# 39-VOLTAGE_SUPERVISOR_AND_WKUP_LEDs.net
KiCad netlist of a schematic drawn in Altium Designer
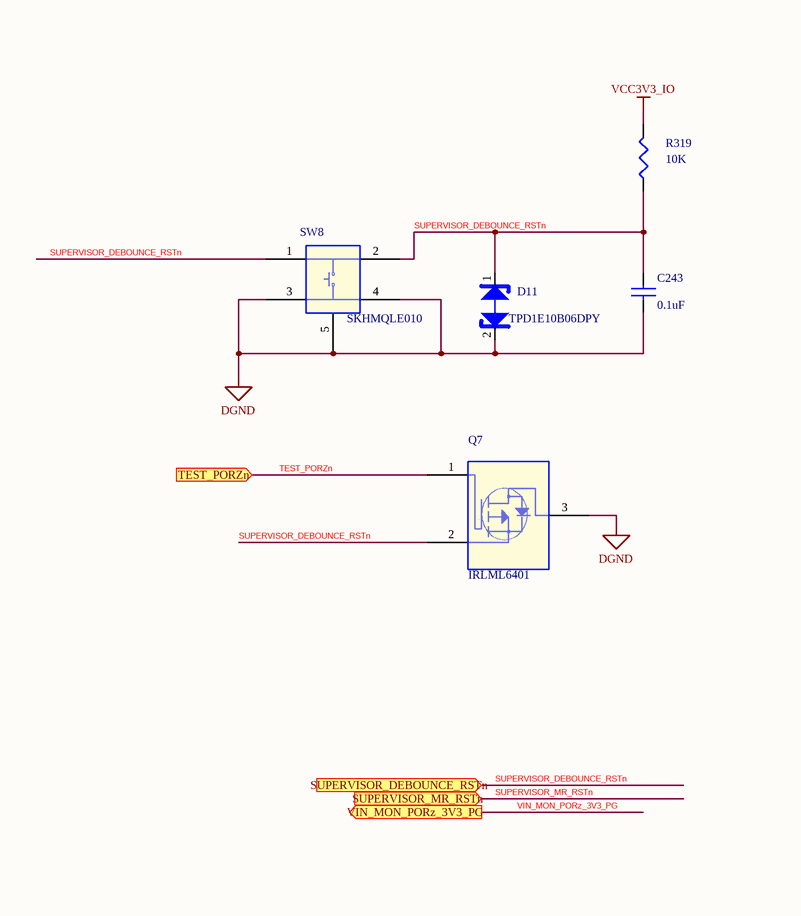
[diagram p0: 39-VOLTAGE SUPERVISOR AND WKUP LEDs.SchDoc, left]
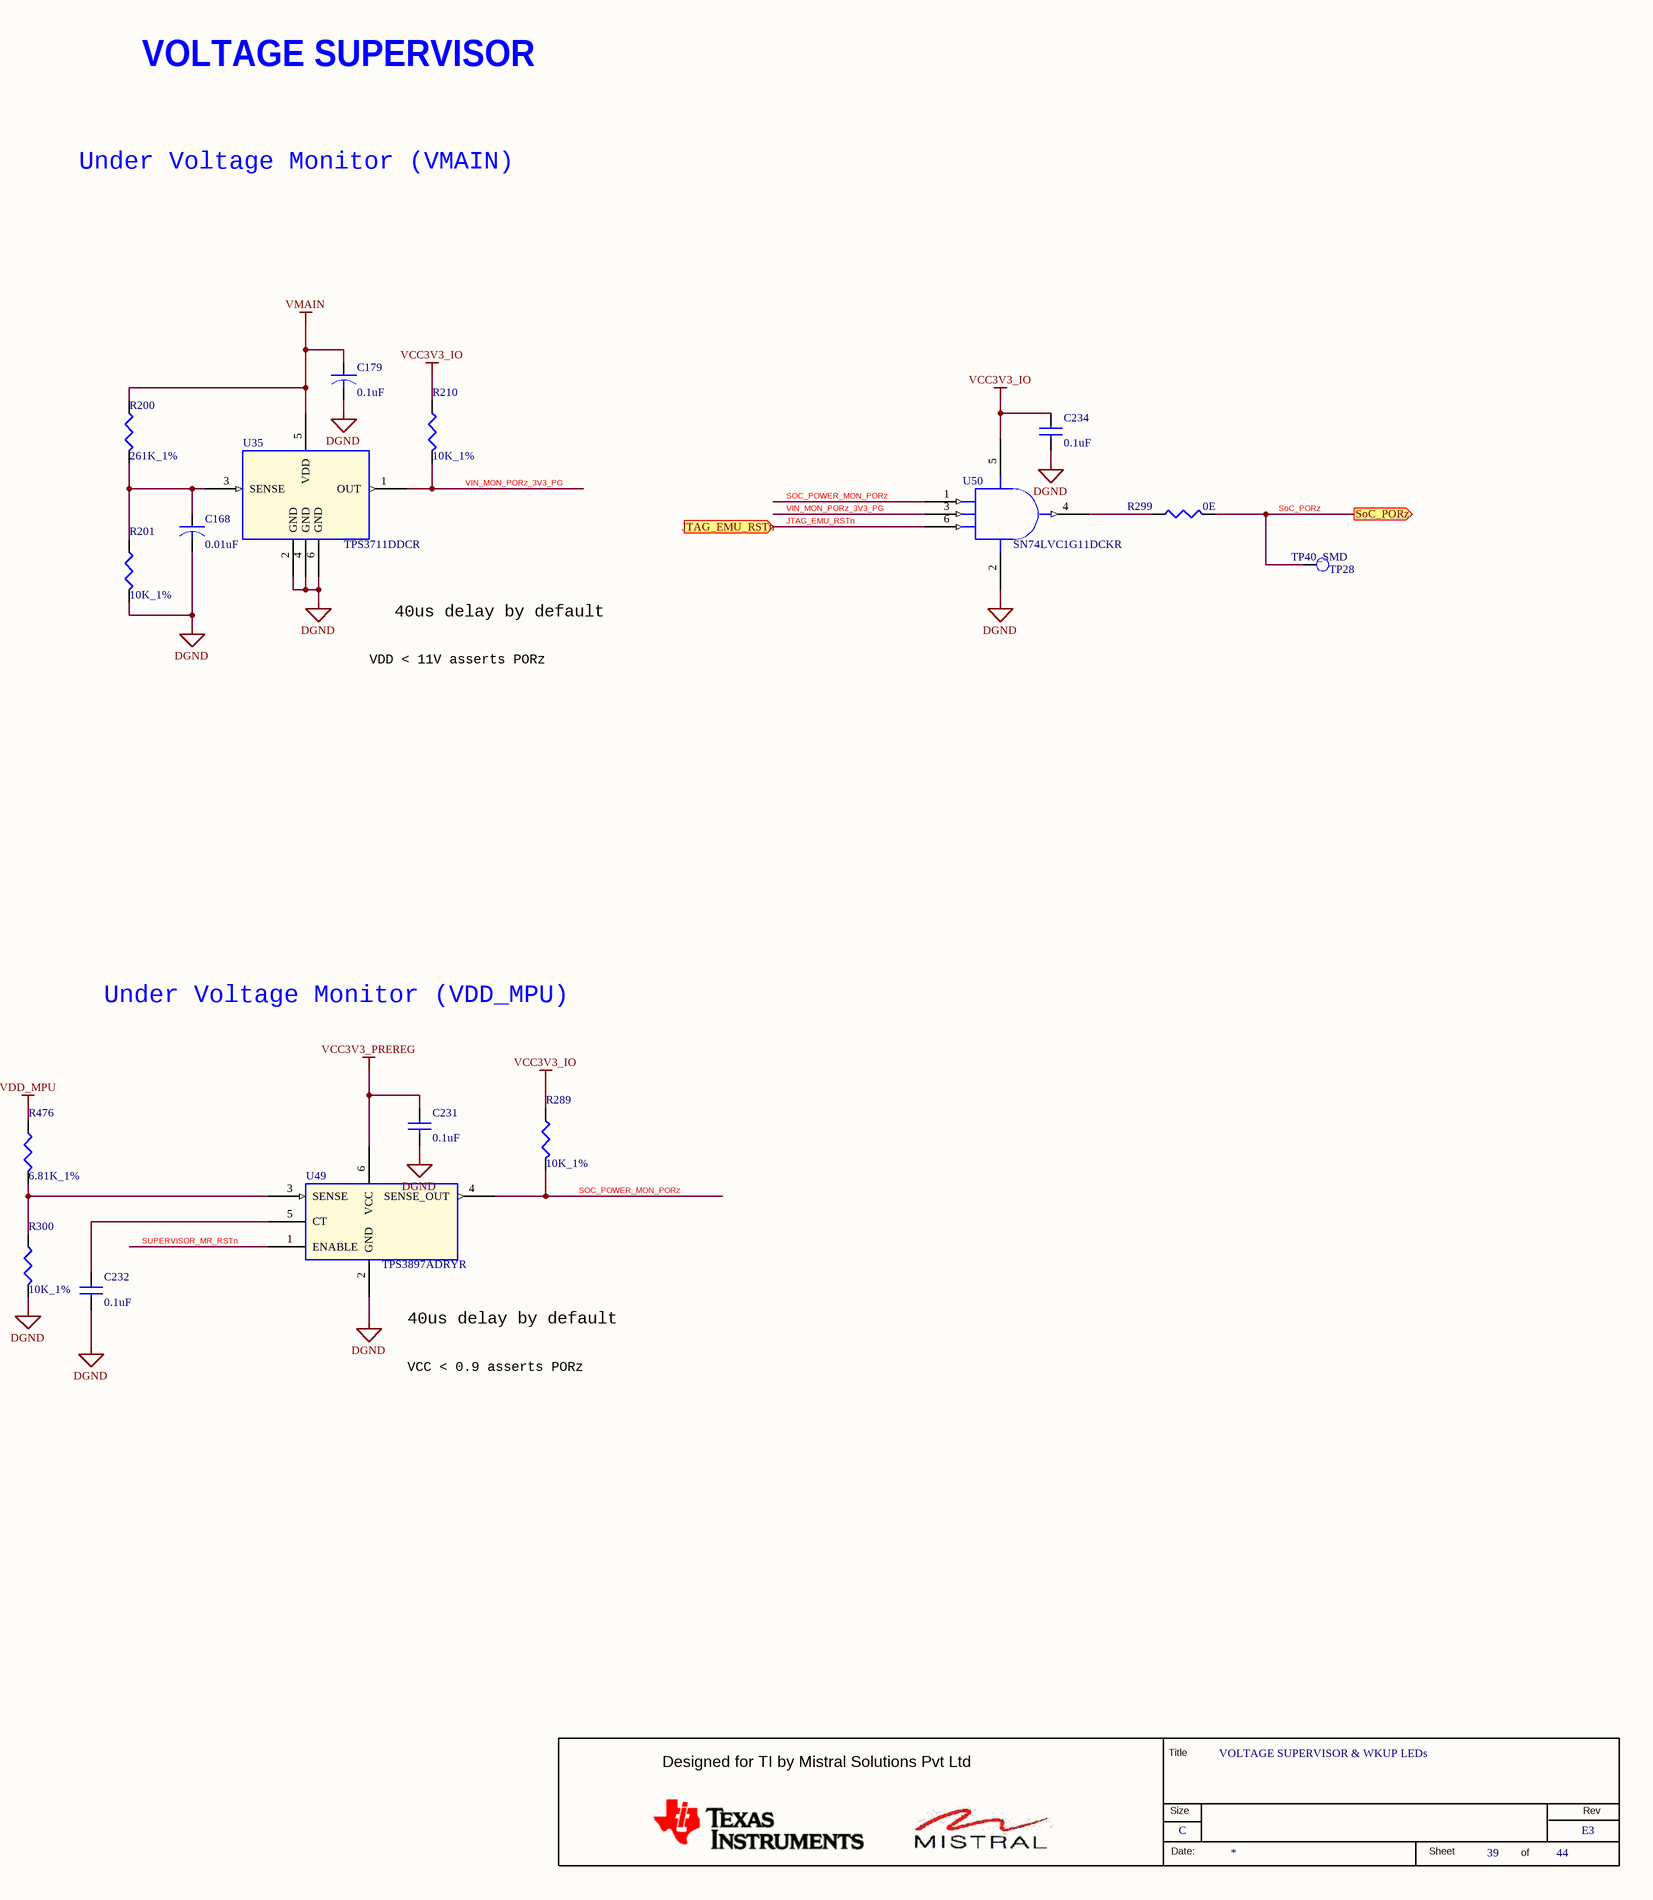
[diagram p1: 39-VOLTAGE SUPERVISOR AND WKUP LEDs.SchDoc, right]

(export (version "E")
  (design (tool "Eeschema 10.0.6"))
  (components
    (comp (ref "C168")
      (value "0.01uF")
      (footprint "CAP0201_0-5")
      (description "CAP CERAMIC 0.01uF 25V 10% X5R 0201")
      (fields
        (field (name "MISTRAL PART NO") "120018010007-R")
        (field (name "MFR_PART_NUMBER") "GRM033R61E103KA12J")
      )
      (libsource (lib "*") (part "CAP"))
    )
    (comp (ref "C179")
      (value "0.1uF")
      (footprint "CAP0603_1")
      (description "CAP CERAMIC 0.1uF 50V 20% X7R 0603")
      (fields
        (field (name "MISTRAL PART NO") "120018010021-R")
        (field (name "MFR_PART_NUMBER") "C0603C104M5RACTU")
      )
      (libsource (lib "*") (part "CAP_Dup1"))
    )
    (comp (ref "C231")
      (value "0.1uF")
      (footprint "CAP0201_0-5")
      (description "CAP CERAMIC 0.1uF 16V 10% X5R 0201")
      (fields (field (name "DISTRIBUTOR_PART_NUMBER") "490-16742-1-ND") (field (name "VOLTAGE") "16V"))
      (libsource (lib "*") (part "CAP_Dup4"))
    )
    (comp (ref "C232")
      (value "0.1uF")
      (footprint "CAP0201_0-5")
      (description "CAP CERAMIC 0.1uF 16V 10% X5R 0201")
      (fields (field (name "DISTRIBUTOR_PART_NUMBER") "490-16742-1-ND") (field (name "VOLTAGE") "16V"))
      (libsource (lib "*") (part "CAP_Dup4"))
    )
    (comp (ref "C234")
      (value "0.1uF")
      (footprint "CAP0201_0-5")
      (description "CAP CERAMIC 0.1uF 16V 10% X5R 0201")
      (fields
        (field (name "MISTRAL PART NO") "120009030072-R")
        (field (name "MFR_PART_NUMBER") "GRM033R61C104KE84J")
      )
      (libsource (lib "*") (part "CAP_Dup4"))
    )
    (comp (ref "C243")
      (value "0.1uF")
      (footprint "CAP0201_0-5")
      (description "CAP CERAMIC 0.1uF 16V 10% X5R 0201")
      (fields (field (name "DISTRIBUTOR_PART_NUMBER") "490-16742-1-ND") (field (name "VOLTAGE") "16V"))
      (libsource (lib "*") (part "CAP_Dup5"))
    )
    (comp (ref "D11")
      (value "TPD1E10B06DPY")
      (footprint "DIO_DFN0402")
      (description "DIODE 1CH ESD PROTECTION SMD(0402)")
      (fields (field (name "MISTRAL PART NO") "130014110022-R") (field (name "TOLERANCE") "NA"))
      (libsource (lib "*") (part "DIODE_PESD"))
    )
    (comp (ref "Q7")
      (value "IRLML6401")
      (footprint "TO_SOT23-123")
      (description "TRANSISTOR MOSFET P-CHANNEL SOT23-3")
      (fields (field (name "DISTRIBUTOR_PART_NUMBER") "IRLML6401PBFCT-ND") (field (name "VOLTAGE") "NA"))
      (libsource (lib "*") (part "MOSFET_IRLML6401TR"))
    )
    (comp (ref "R200")
      (value "261K_1%")
      (footprint "RES0402_0-5")
      (description "RES 261K 1/16W 1% 0402")
      (fields
        (field (name "MISTRAL PART NO") "110015080042-R")
        (field (name "MFR_PART_NUMBER") "RC0402FR-07261KL")
      )
      (libsource (lib "*") (part "RESISTOR_Dup5"))
    )
    (comp (ref "R201")
      (value "10K_1%")
      (footprint "RES0402_0-5")
      (description "RES 10K 1/16W 1% 0402")
      (fields
        (field (name "MISTRAL PART NO") "110009030220-P")
        (field (name "MFR_PART_NUMBER") "RC0402FR-0710KL")
      )
      (libsource (lib "*") (part "RESISTOR_Dup5"))
    )
    (comp (ref "R210")
      (value "10K_1%")
      (footprint "RES0402_0-5")
      (description "RES 10K 1/16W 1% 0402")
      (fields (field (name "DISTRIBUTOR_PART_NUMBER") "311-10.0KLRTR-ND") (field (name "TOLERANCE") "1%"))
      (libsource (lib "*") (part "RESISTOR_Dup4"))
    )
    (comp (ref "R289")
      (value "10K_1%")
      (footprint "RES0402_0-5")
      (description "RES 10K 1/16W 1% 0402")
      (fields (field (name "DISTRIBUTOR_PART_NUMBER") "311-10.0KLRTR-ND") (field (name "TOLERANCE") "1%"))
      (libsource (lib "*") (part "RESISTOR_Dup4"))
    )
    (comp (ref "R299")
      (value "0E")
      (footprint "RES0402_0-5")
      (description "RES 0E 1/16W 0402")
      (fields (field (name "DISTRIBUTOR_PART_NUMBER") "541-0.0JCT-ND") (field (name "VOLTAGE") "NA"))
      (libsource (lib "*") (part "RESISTOR_Dup5"))
    )
    (comp (ref "R300")
      (value "10K_1%")
      (footprint "RES0402_0-5")
      (description "RES 10K 1/16W 1% 0402")
      (fields (field (name "DISTRIBUTOR_PART_NUMBER") "311-10.0KLRTR-ND") (field (name "TOLERANCE") "1%"))
      (libsource (lib "*") (part "RESISTOR_Dup4"))
    )
    (comp (ref "R319")
      (value "10K")
      (footprint "RES0402_0-5")
      (description "RES 10K 1/16W 5% 0402")
      (fields (field (name "DISTRIBUTOR_PART_NUMBER") "311-10KJRCT-ND") (field (name "VOLTAGE") "NA"))
      (libsource (lib "*") (part "RESISTOR_Dup5"))
    )
    (comp (ref "R476")
      (value "6.81K_1%")
      (footprint "RES0402_0-5")
      (description "RES 6.81K 1/16W 1% 0402")
      (fields (field (name "DISTRIBUTOR_PART_NUMBER") "311-6.81KLRCT-ND") (field (name "VOLTAGE") "NA"))
      (libsource (lib "*") (part "RESISTOR"))
    )
    (comp (ref "SW8")
      (value "SKHMQLE010")
      (footprint "SW4_SKHMQLE010_240X260_SMD_3-1")
      (description "SWITCH TACTILE SPST ST SMD")
      (fields (field (name "DISTRIBUTOR_PART_NUMBER") "688-SKHMQLE010") (field (name "VOLTAGE") "NA"))
      (libsource (lib "*") (part "SW4_SKHUPLE010"))
    )
    (comp (ref "TP28")
      (value "TP40_SMD")
      (footprint "TP40_SMD")
      (description "TESTPOINT CIR 40 SMD")
      (fields (field (name "DISTRIBUTOR_PART_NUMBER") "NA") (field (name "MISTRAL PART NO") "130009030933"))
      (libsource (lib "*") (part "TESTPOINT"))
    )
    (comp (ref "U35")
      (value "TPS3711DDCR")
      (footprint "SOT23-6_1-1")
      (description "IC 36V VOLTAGE DETECTOR SOT23-6")
      (fields (field (name "DISTRIBUTOR_PART_NUMBER") "296-43278-1-ND") (field (name "VOLTAGE") "NA"))
      (libsource (lib "*") (part "TPS3711DDCR_SOT23-6"))
    )
    (comp (ref "U49")
      (value "TPS3897ADRYR")
      (footprint "SON6_19-68_40X60_0-6")
      (description "IC 1-CH ADJ VOLTAGE MONITOR SON6")
      (fields (field (name "MISTRAL PART NO") "142017100007-R") (field (name "TOLERANCE") "NA"))
      (libsource (lib "*") (part "TPS3897ADRYR_SON6"))
    )
    (comp (ref "U50")
      (value "SN74LVC1G11DCKR")
      (footprint "SC70-6")
      (description "IC SINGLE 3-INPUT POSITIVE-AND GATE SC70-6")
      (fields
        (field (name "MISTRAL PART NO") "141009030230-R")
        (field (name "DISTRIBUTOR_PART_NUMBER") "296-18066-1-ND")
      )
      (libsource (lib "*") (part "SN74LVC1G11DCKR_SC70-6"))
    )
  )
  (nets
    (net (code "1") (name "/JTAG_EMU_RSTn") (class "Default")
      (node (ref "U50") (pin "6") (pinfunction "C_6") (pintype "input"))
    )
    (net (code "2") (name "/SOC_POWER_MON_PORz") (class "Default")
      (node (ref "R289") (pin "2") (pinfunction "2_2") (pintype "passive"))
      (node (ref "U49") (pin "4") (pinfunction "SENSE_OUT_4") (pintype "output"))
      (node (ref "U50") (pin "1") (pinfunction "A_1") (pintype "input"))
    )
    (net (code "3") (name "/SUPERVISOR_DEBOUNCE_RSTn") (class "Default")
      (node (ref "C243") (pin "1") (pinfunction "1_1") (pintype "passive"))
      (node (ref "D11") (pin "1") (pinfunction "K_1") (pintype "passive"))
      (node (ref "Q7") (pin "2") (pinfunction "S_2") (pintype "passive"))
      (node (ref "R319") (pin "1") (pinfunction "1_1") (pintype "passive"))
      (node (ref "SW8") (pin "1") (pinfunction "1_1") (pintype "passive"))
      (node (ref "SW8") (pin "2") (pinfunction "2_2") (pintype "passive"))
    )
    (net (code "4") (name "/SUPERVISOR_MR_RSTn") (class "Default")
      (node (ref "U49") (pin "1") (pinfunction "ENABLE_1") (pintype "passive"))
    )
    (net (code "5") (name "/SoC_PORz") (class "Default")
      (node (ref "R299") (pin "2") (pinfunction "2_2") (pintype "passive"))
      (node (ref "TP28") (pin "1") (pinfunction "TP_1") (pintype "passive"))
    )
    (net (code "6") (name "/TEST_PORZn") (class "Default")
      (node (ref "Q7") (pin "1") (pinfunction "G_1") (pintype "passive"))
    )
    (net (code "7") (name "/VIN_MON_PORz_3V3_PG") (class "Default")
      (node (ref "R210") (pin "2") (pinfunction "2_2") (pintype "passive"))
      (node (ref "U35") (pin "1") (pinfunction "OUT_1") (pintype "output"))
      (node (ref "U50") (pin "3") (pinfunction "B_3") (pintype "input"))
    )
    (net (code "8") (name "DGND") (class "Default")
      (node (ref "C168") (pin "2") (pinfunction "2_2") (pintype "passive"))
      (node (ref "C179") (pin "2") (pinfunction "2_2") (pintype "passive"))
      (node (ref "C231") (pin "2") (pinfunction "2_2") (pintype "passive"))
      (node (ref "C232") (pin "2") (pinfunction "2_2") (pintype "passive"))
      (node (ref "C234") (pin "2") (pinfunction "2_2") (pintype "passive"))
      (node (ref "C243") (pin "2") (pinfunction "2_2") (pintype "passive"))
      (node (ref "D11") (pin "2") (pinfunction "A_2") (pintype "passive"))
      (node (ref "Q7") (pin "3") (pinfunction "D_3") (pintype "passive"))
      (node (ref "R201") (pin "2") (pinfunction "2_2") (pintype "passive"))
      (node (ref "R300") (pin "2") (pinfunction "2_2") (pintype "passive"))
      (node (ref "SW8") (pin "3") (pinfunction "3_3") (pintype "passive"))
      (node (ref "SW8") (pin "4") (pinfunction "4_4") (pintype "passive"))
      (node (ref "SW8") (pin "5") (pinfunction "GND_5") (pintype "power_in"))
      (node (ref "U35") (pin "2") (pinfunction "GND_2") (pintype "power_in"))
      (node (ref "U35") (pin "4") (pinfunction "GND_4") (pintype "power_in"))
      (node (ref "U35") (pin "6") (pinfunction "GND_6") (pintype "power_in"))
      (node (ref "U49") (pin "2") (pinfunction "GND_2") (pintype "power_in"))
      (node (ref "U50") (pin "2") (pinfunction "GND_2") (pintype "power_in"))
    )
    (net (code "9") (name "Net-(U35-SENSE)") (class "Default")
      (node (ref "C168") (pin "1") (pinfunction "1_1") (pintype "passive"))
      (node (ref "R200") (pin "2") (pinfunction "2_2") (pintype "passive"))
      (node (ref "R201") (pin "1") (pinfunction "1_1") (pintype "passive"))
      (node (ref "U35") (pin "3") (pinfunction "SENSE_3") (pintype "input"))
    )
    (net (code "10") (name "Net-(U49-CT)") (class "Default")
      (node (ref "C232") (pin "1") (pinfunction "1_1") (pintype "passive"))
      (node (ref "U49") (pin "5") (pinfunction "CT_5") (pintype "passive"))
    )
    (net (code "11") (name "Net-(U49-SENSE)") (class "Default")
      (node (ref "R300") (pin "1") (pinfunction "1_1") (pintype "passive"))
      (node (ref "R476") (pin "2") (pinfunction "2_2") (pintype "passive"))
      (node (ref "U49") (pin "3") (pinfunction "SENSE_3") (pintype "input"))
    )
    (net (code "12") (name "Net-(U50-Y)") (class "Default")
      (node (ref "R299") (pin "1") (pinfunction "1_1") (pintype "passive"))
      (node (ref "U50") (pin "4") (pinfunction "Y_4") (pintype "output"))
    )
    (net (code "13") (name "VCC3V3_IO") (class "Default")
      (node (ref "C234") (pin "1") (pinfunction "1_1") (pintype "passive"))
      (node (ref "R210") (pin "1") (pinfunction "1_1") (pintype "passive"))
      (node (ref "R289") (pin "1") (pinfunction "1_1") (pintype "passive"))
      (node (ref "R319") (pin "2") (pinfunction "2_2") (pintype "passive"))
      (node (ref "U50") (pin "5") (pinfunction "VCC_5") (pintype "power_in"))
    )
    (net (code "14") (name "VCC3V3_PREREG") (class "Default")
      (node (ref "C231") (pin "1") (pinfunction "1_1") (pintype "passive"))
      (node (ref "U49") (pin "6") (pinfunction "VCC_6") (pintype "power_in"))
    )
    (net (code "15") (name "VDD_MPU") (class "Default")
      (node (ref "R476") (pin "1") (pinfunction "1_1") (pintype "passive"))
    )
    (net (code "16") (name "VMAIN") (class "Default")
      (node (ref "C179") (pin "1") (pinfunction "1_1") (pintype "passive"))
      (node (ref "R200") (pin "1") (pinfunction "1_1") (pintype "passive"))
      (node (ref "U35") (pin "5") (pinfunction "VDD_5") (pintype "power_in"))
    )
  )
)
